# Microfono.net
KiCad netlist of a schematic drawn in Altium Designer
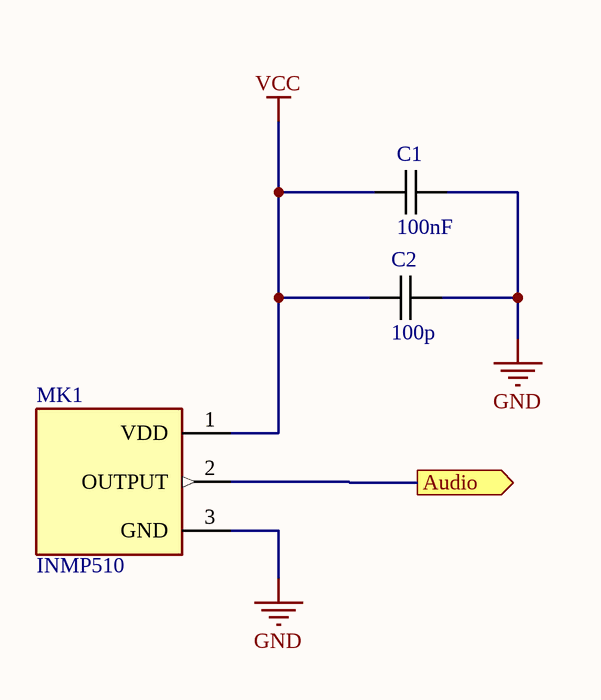
[diagram p0: Microfono.SchDoc]

(export (version "E")
  (design (tool "Eeschema 10.0.6"))
  (components
    (comp (ref "C1")
      (value "100nF")
      (footprint "0805C-TBD")
      (description "CAPACITOR 0805 CERAMIC")
      (libsource (lib "vh_altium_library") (part "0805C-100nF-25V-X7R-MUR"))
    )
    (comp (ref "C2")
      (value "100p")
      (footprint "0805C-GENERIC")
      (description "GENERIC CAPACITOR NON POLARISED0603")
      (libsource (lib "vh_altium_library") (part "C0805-GENERIC"))
    )
    (comp (ref "MK1")
      (value "INMP510")
      (footprint "XDCR_INMP510")
      (fields (field (name "DIGI-KEY_PART_NUMBER") "1428-1016-2-ND") (field (name "MF") "TDK InvenSense"))
      (libsource (lib "INMP510") (part "INMP510"))
    )
  )
  (nets
    (net (code "1") (name "/Audio") (class "Default")
      (node (ref "MK1") (pin "2") (pinfunction "OUTPUT_2") (pintype "output"))
    )
    (net (code "2") (name "GND") (class "Default")
      (node (ref "C1") (pin "2") (pintype "passive"))
      (node (ref "C2") (pin "2") (pintype "passive"))
      (node (ref "MK1") (pin "3") (pinfunction "GND_3") (pintype "power_in"))
    )
    (net (code "3") (name "VCC") (class "Default")
      (node (ref "C1") (pin "1") (pintype "passive"))
      (node (ref "C2") (pin "1") (pintype "passive"))
      (node (ref "MK1") (pin "1") (pinfunction "VDD_1") (pintype "power_in"))
    )
  )
)
